# Supply.net
KiCad netlist of a schematic drawn in Altium Designer
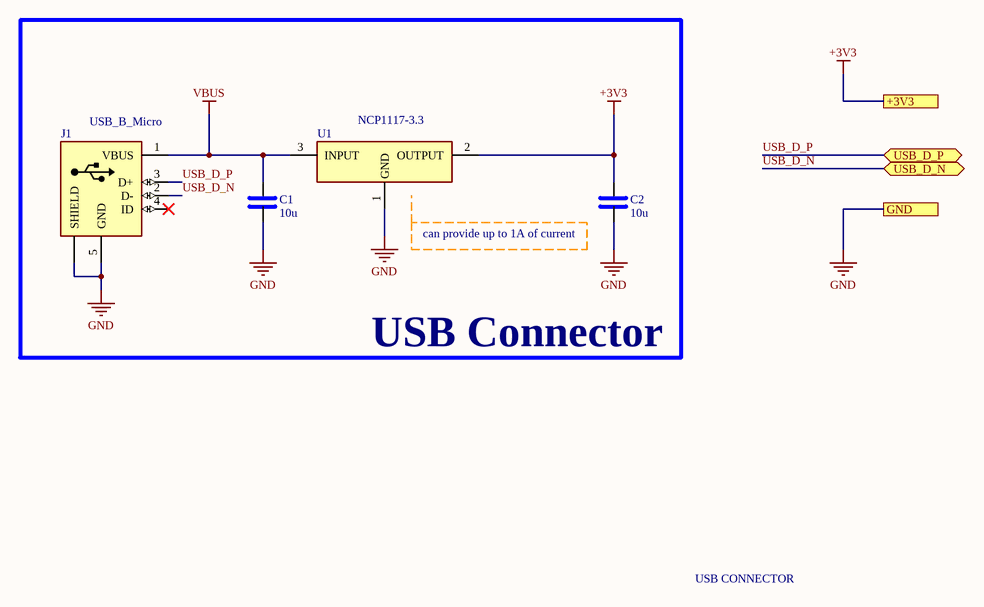
[diagram p0: Supply.SchDoc]

(export (version "E")
  (design (tool "Eeschema 10.0.6"))
  (components
    (comp (ref "C1")
      (value "10u")
      (footprint "VJ0805")
      (fields
        (field (name "MANUFACTURER") "Murata")
        (field (name "MANUFACTURER PART NUMBER") "GRM21BR61E106KA73K")
      )
      (libsource (lib "Schlib") (part "0805 SMD Capacitor"))
    )
    (comp (ref "C2")
      (value "10u")
      (footprint "VJ0805")
      (fields
        (field (name "MANUFACTURER") "Murata")
        (field (name "MANUFACTURER PART NUMBER") "GRM21BR61E106KA73K")
      )
      (libsource (lib "Schlib") (part "0805 SMD Capacitor"))
    )
    (comp (ref "J1")
      (value "USB_B_Micro")
      (footprint "MOLEX_1050170002")
      (description "Micro-USB B Receptacle, Bottom Mount, Surface Mount with Solder Tabs, Lead-Free")
      (fields (field (name "MF") "Molex") (field (name "MP") "1050170002"))
      (libsource (lib "Integrated_Library") (part "USB_B_Micro"))
    )
    (comp (ref "U1")
      (value "NCP1117-3.3")
      (footprint "VREG_NCP1117STAT3")
      (description "Linear Voltage Regulator IC Positive Adjustable 1 Output 1A SOT-223")
      (fields (field (name "MF") "ON Semiconductor") (field (name "MP") "NCP1117STAT3"))
      (libsource (lib "Integrated_Library") (part "NCP1117-3.3"))
    )
  )
  (nets
    (net (code "1") (name "+3V3") (class "Default")
      (node (ref "C2") (pin "2") (pinfunction "2_2") (pintype "passive"))
      (node (ref "U1") (pin "2") (pinfunction "OUTPUT_2") (pintype "power_in"))
    )
    (net (code "2") (name "/USB_D_N") (class "Default")
      (node (ref "J1") (pin "2") (pinfunction "D-_2") (pintype "bidirectional"))
    )
    (net (code "3") (name "/USB_D_P") (class "Default")
      (node (ref "J1") (pin "3") (pinfunction "D+_3") (pintype "bidirectional"))
    )
    (net (code "4") (name "GND") (class "Default")
      (node (ref "C1") (pin "1") (pinfunction "1_1") (pintype "passive"))
      (node (ref "C2") (pin "1") (pinfunction "1_1") (pintype "passive"))
      (node (ref "J1") (pin "5") (pinfunction "GND_5") (pintype "power_in"))
      (node (ref "J1") (pin "SH") (pinfunction "SHIELD_SH") (pintype "passive"))
      (node (ref "U1") (pin "1") (pinfunction "GND_1") (pintype "power_in"))
    )
    (net (code "5") (name "VBUS") (class "Default")
      (node (ref "C1") (pin "2") (pinfunction "2_2") (pintype "passive"))
      (node (ref "J1") (pin "1") (pinfunction "VBUS_1") (pintype "power_in"))
      (node (ref "U1") (pin "3") (pinfunction "INPUT_3") (pintype "power_in"))
    )
    (net (code "6") (name "unconnected-(J1-ID-Pad4)") (class "Default")
      (node (ref "J1") (pin "4") (pinfunction "ID_4") (pintype "bidirectional+no_connect"))
    )
  )
)
